# SchematProcesor.net
KiCad netlist of a schematic drawn in EAGLE
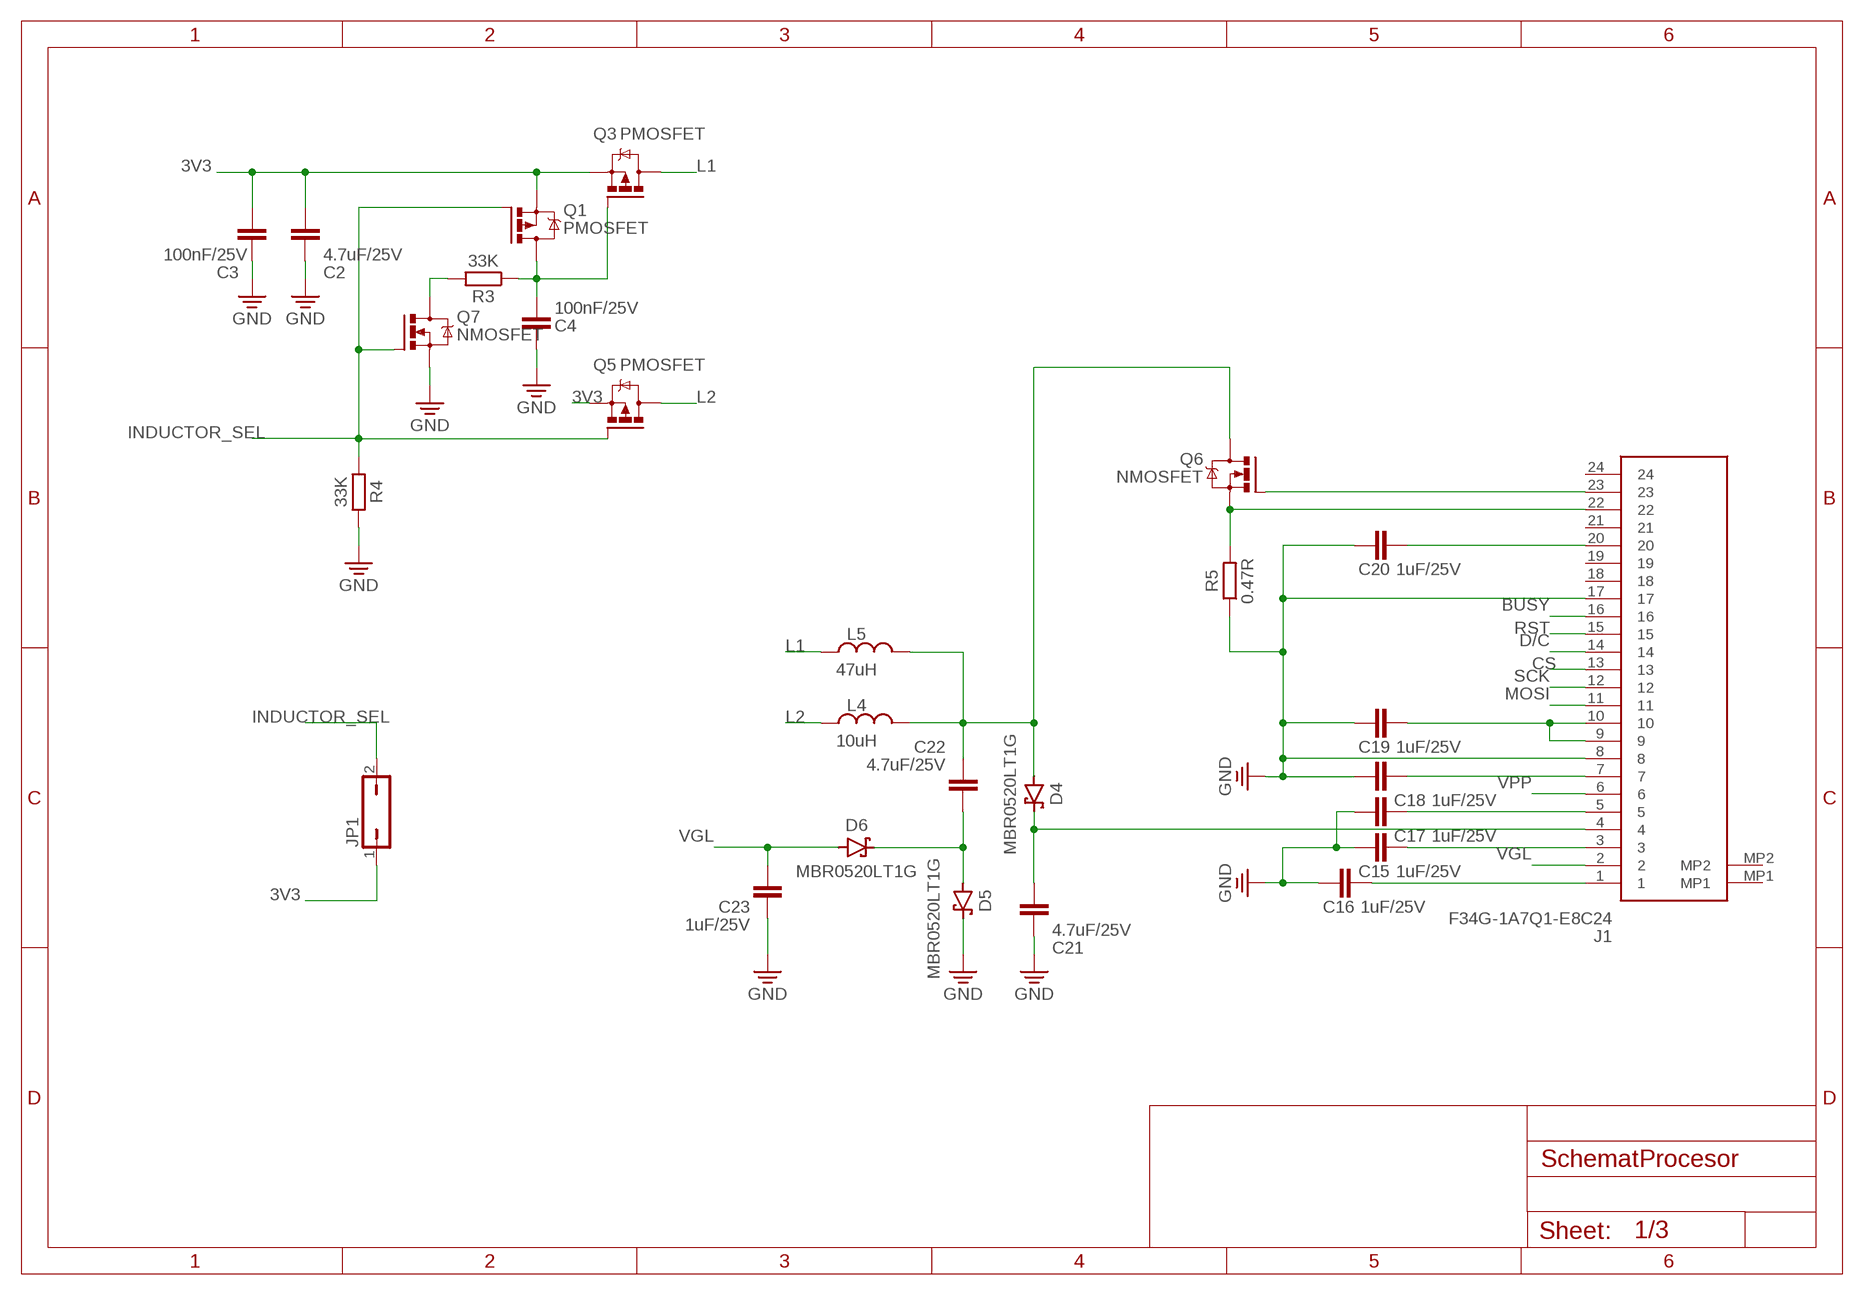
[diagram p0: schematic, sheet 1]
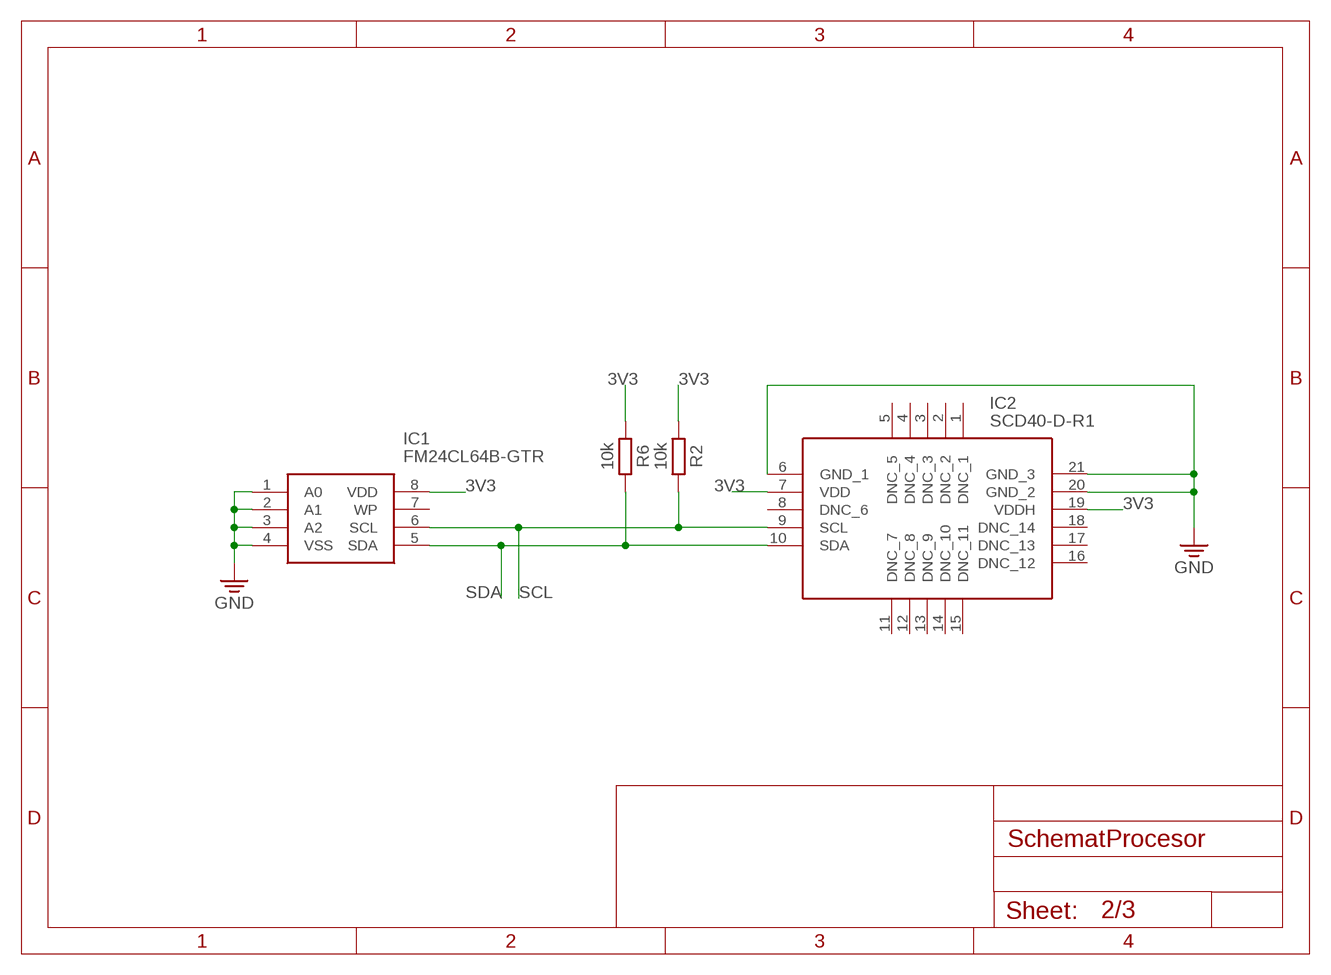
[diagram p1: schematic, sheet 2]
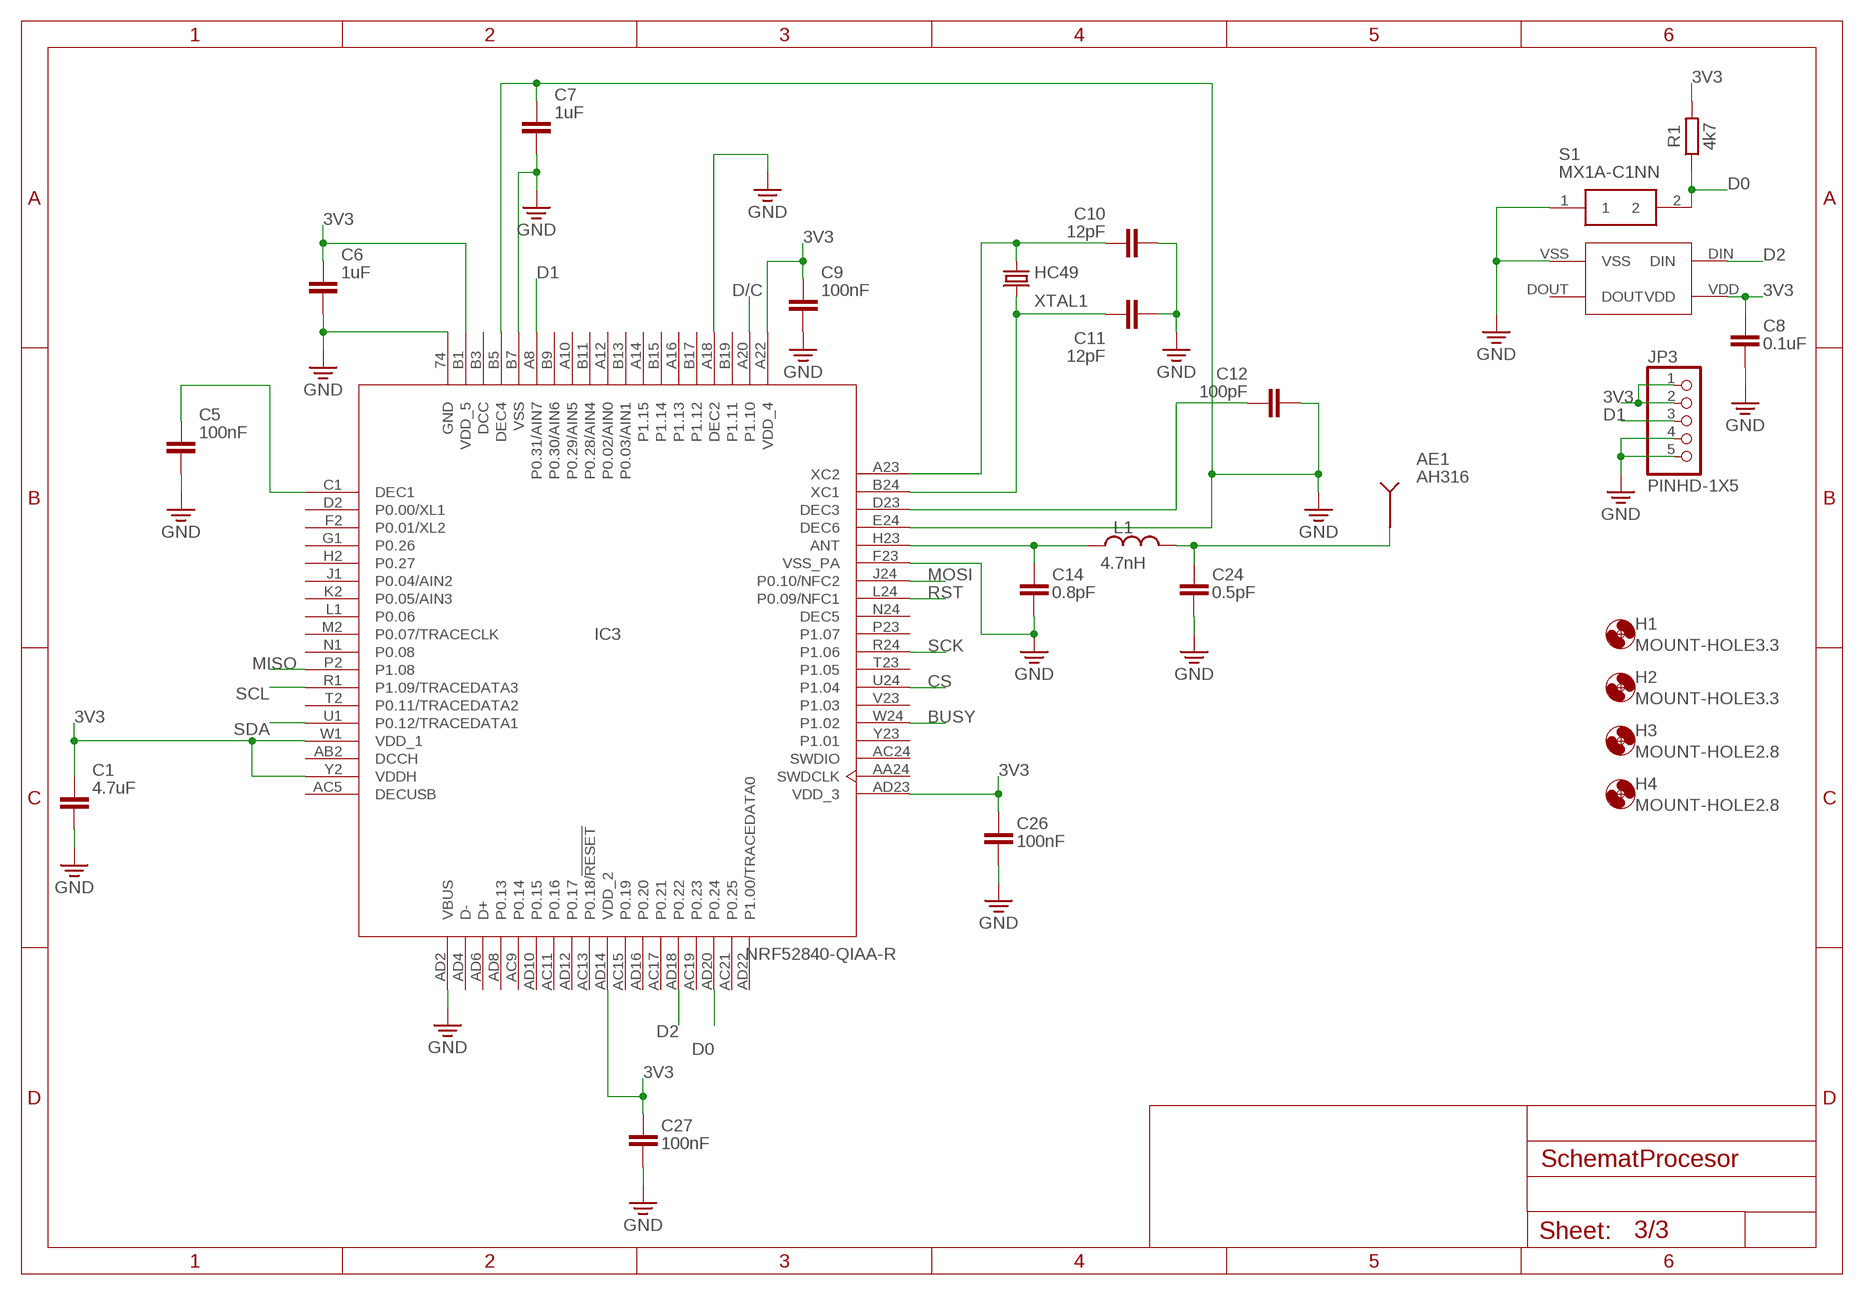
[diagram p2: schematic, sheet 3]

(export (version "E")
  (design (tool "Eeschema 10.0.6"))
  (components
    (comp (ref "C2")
      (value "4.7uF/25V")
      (footprint "eagle-import:CAPC1608X85")
      (libsource (lib "eagle-import") (part "CCHIP-0603(1608-METRIC)_"))
    )
    (comp (ref "C3")
      (value "100nF/25V")
      (footprint "eagle-import:CAPC1608X85")
      (libsource (lib "eagle-import") (part "CCHIP-0603(1608-METRIC)_"))
    )
    (comp (ref "C4")
      (value "100nF/25V")
      (footprint "eagle-import:CAPC1608X85")
      (libsource (lib "eagle-import") (part "CCHIP-0603(1608-METRIC)_"))
    )
    (comp (ref "C15")
      (value "1uF/25V")
      (footprint "eagle-import:CAPC1608X85")
      (libsource (lib "eagle-import") (part "CCHIP-0603(1608-METRIC)_"))
    )
    (comp (ref "C16")
      (value "1uF/25V")
      (footprint "eagle-import:CAPC1608X85")
      (libsource (lib "eagle-import") (part "CCHIP-0603(1608-METRIC)_"))
    )
    (comp (ref "C17")
      (value "1uF/25V")
      (footprint "eagle-import:CAPC1608X85")
      (libsource (lib "eagle-import") (part "CCHIP-0603(1608-METRIC)_"))
    )
    (comp (ref "C18")
      (value "1uF/25V")
      (footprint "eagle-import:CAPC1608X85")
      (libsource (lib "eagle-import") (part "CCHIP-0603(1608-METRIC)_"))
    )
    (comp (ref "C19")
      (value "1uF/25V")
      (footprint "eagle-import:CAPC1608X85")
      (libsource (lib "eagle-import") (part "CCHIP-0603(1608-METRIC)_"))
    )
    (comp (ref "C20")
      (value "1uF/25V")
      (footprint "eagle-import:CAPC1608X85")
      (libsource (lib "eagle-import") (part "CCHIP-0603(1608-METRIC)_"))
    )
    (comp (ref "C21")
      (value "4.7uF/25V")
      (footprint "eagle-import:CAPC1608X85")
      (libsource (lib "eagle-import") (part "CCHIP-0603(1608-METRIC)_"))
    )
    (comp (ref "C22")
      (value "4.7uF/25V")
      (footprint "eagle-import:CAPC1608X85")
      (libsource (lib "eagle-import") (part "CCHIP-0603(1608-METRIC)_"))
    )
    (comp (ref "C23")
      (value "1uF/25V")
      (footprint "eagle-import:CAPC1608X85")
      (libsource (lib "eagle-import") (part "CCHIP-0603(1608-METRIC)_"))
    )
    (comp (ref "D4")
      (value "MBR0520LT1G")
      (footprint "eagle-import:SODFL3718X115")
      (fields (field (name "MANUFACTURER") "ON Semiconductor"))
      (libsource (lib "eagle-import") (part "SCHOTTKY_DO-219MBR0520LT1G"))
    )
    (comp (ref "D5")
      (value "MBR0520LT1G")
      (footprint "eagle-import:SODFL3718X115")
      (fields (field (name "MANUFACTURER") "ON Semiconductor"))
      (libsource (lib "eagle-import") (part "SCHOTTKY_DO-219MBR0520LT1G"))
    )
    (comp (ref "D6")
      (value "MBR0520LT1G")
      (footprint "eagle-import:SODFL3718X115")
      (fields (field (name "MANUFACTURER") "ON Semiconductor"))
      (libsource (lib "eagle-import") (part "SCHOTTKY_DO-219MBR0520LT1G"))
    )
    (comp (ref "J1")
      (value "F34G-1A7Q1-E8C24")
      (footprint "eagle-import:F34G1A7Q1E8C24")
      (fields (field (name "MOUSER_PART_NUMBER") "649-F34G1A7Q1E8C24"))
      (libsource (lib "eagle-import") (part "F34G-1A7Q1-E8C24"))
    )
    (comp (ref "JP1")
      (value "JP1Q")
      (footprint "eagle-import:JP1")
      (libsource (lib "eagle-import") (part "JP1Q"))
    )
    (comp (ref "L4")
      (value "10uH")
      (footprint "eagle-import:INDC1608X95N")
      (libsource (lib "eagle-import") (part "LCHIP-0603(1608-METRIC)_"))
    )
    (comp (ref "L5")
      (value "47uH")
      (footprint "eagle-import:INDC1608X95N")
      (libsource (lib "eagle-import") (part "LCHIP-0603(1608-METRIC)_"))
    )
    (comp (ref "Q1")
      (value "PMOSFET")
      (footprint "eagle-import:SOT23")
      (libsource (lib "eagle-import") (part "PMOSFETSOT23-GSD_"))
    )
    (comp (ref "Q3")
      (value "PMOSFET")
      (footprint "eagle-import:SOT23")
      (libsource (lib "eagle-import") (part "PMOSFETSOT23-GSD_"))
    )
    (comp (ref "Q5")
      (value "PMOSFET")
      (footprint "eagle-import:SOT23")
      (libsource (lib "eagle-import") (part "PMOSFETSOT23-GSD_"))
    )
    (comp (ref "Q6")
      (value "NMOSFET")
      (footprint "eagle-import:SOT23")
      (libsource (lib "eagle-import") (part "NMOSFETSOT23-GSD"))
    )
    (comp (ref "Q7")
      (value "NMOSFET")
      (footprint "eagle-import:SOT23")
      (libsource (lib "eagle-import") (part "NMOSFETSOT23-GSD"))
    )
    (comp (ref "R3")
      (value "33K")
      (footprint "eagle-import:RESC1608X60")
      (libsource (lib "eagle-import") (part "RCHIP-0603(1608-METRIC)_"))
    )
    (comp (ref "R4")
      (value "33K")
      (footprint "eagle-import:RESC1608X60")
      (libsource (lib "eagle-import") (part "RCHIP-0603(1608-METRIC)_"))
    )
    (comp (ref "R5")
      (value "0.47R")
      (footprint "eagle-import:RESC1608X60")
      (libsource (lib "eagle-import") (part "RCHIP-0603(1608-METRIC)_"))
    )
    (comp (ref "IC1")
      (value "FM24CL64B-GTR")
      (footprint "eagle-import:SOIC127P602X173-8N")
      (fields (field (name "MOUSER_PART_NUMBER") "877-FM24CL64B-GTR"))
      (libsource (lib "eagle-import") (part "FM24CL64B-GTR"))
    )
    (comp (ref "IC2")
      (value "SCD40-D-R1")
      (footprint "eagle-import:SCD40DR1")
      (fields (field (name "MOUSER_PART_NUMBER") "403-SCD40-D-R1"))
      (libsource (lib "eagle-import") (part "SCD40-D-R1"))
    )
    (comp (ref "R2")
      (value "10k")
      (footprint "eagle-import:RESC1608X60")
      (libsource (lib "eagle-import") (part "RCHIP-0603(1608-METRIC)_"))
    )
    (comp (ref "R6")
      (value "10k")
      (footprint "eagle-import:RESC1608X60")
      (libsource (lib "eagle-import") (part "RCHIP-0603(1608-METRIC)_"))
    )
    (comp (ref "AE1")
      (value "AH316")
      (footprint "eagle-import:ANT-GPS-3.2X1MM")
      (fields (field (name "MANUFACTURER") "Taiyo Yuden") (field (name "MPN") "AH316M245001-T"))
      (libsource (lib "eagle-import") (part "AH316"))
    )
    (comp (ref "C1")
      (value "4.7uF")
      (footprint "eagle-import:CAPC1608X85")
      (libsource (lib "eagle-import") (part "CCHIP-0603(1608-METRIC)_"))
    )
    (comp (ref "C5")
      (value "100nF")
      (footprint "eagle-import:CAPC1608X85")
      (libsource (lib "eagle-import") (part "CCHIP-0603(1608-METRIC)_"))
    )
    (comp (ref "C6")
      (value "1uF")
      (footprint "eagle-import:CAPC1608X85")
      (libsource (lib "eagle-import") (part "CCHIP-0603(1608-METRIC)_"))
    )
    (comp (ref "C7")
      (value "1uF")
      (footprint "eagle-import:CAPC1608X85")
      (libsource (lib "eagle-import") (part "CCHIP-0603(1608-METRIC)_"))
    )
    (comp (ref "C8")
      (value "0.1uF")
      (footprint "eagle-import:CAPC1608X85")
      (libsource (lib "eagle-import") (part "CCHIP-0603(1608-METRIC)_"))
    )
    (comp (ref "C9")
      (value "100nF")
      (footprint "eagle-import:CAPC1608X85")
      (libsource (lib "eagle-import") (part "CCHIP-0603(1608-METRIC)_"))
    )
    (comp (ref "C10")
      (value "12pF")
      (footprint "eagle-import:CAPC1608X85")
      (libsource (lib "eagle-import") (part "CCHIP-0603(1608-METRIC)_"))
    )
    (comp (ref "C11")
      (value "12pF")
      (footprint "eagle-import:CAPC1608X85")
      (libsource (lib "eagle-import") (part "CCHIP-0603(1608-METRIC)_"))
    )
    (comp (ref "C12")
      (value "100pF")
      (footprint "eagle-import:CAPC1608X85")
      (libsource (lib "eagle-import") (part "CCHIP-0603(1608-METRIC)_"))
    )
    (comp (ref "C14")
      (value "0.8pF")
      (footprint "eagle-import:CAPC1608X85")
      (libsource (lib "eagle-import") (part "CCHIP-0603(1608-METRIC)_"))
    )
    (comp (ref "C24")
      (value "0.5pF")
      (footprint "eagle-import:CAPC1608X85")
      (libsource (lib "eagle-import") (part "CCHIP-0603(1608-METRIC)_"))
    )
    (comp (ref "C26")
      (value "100nF")
      (footprint "eagle-import:CAPC1608X85")
      (libsource (lib "eagle-import") (part "CCHIP-0603(1608-METRIC)_"))
    )
    (comp (ref "C27")
      (value "100nF")
      (footprint "eagle-import:CAPC1608X85")
      (libsource (lib "eagle-import") (part "CCHIP-0603(1608-METRIC)_"))
    )
    (comp (ref "H1")
      (value "MOUNT-HOLE3.3")
      (footprint "eagle-import:3,3")
      (libsource (lib "eagle-import") (part "MOUNT-HOLE3.3"))
    )
    (comp (ref "H2")
      (value "MOUNT-HOLE3.3")
      (footprint "eagle-import:3,3")
      (libsource (lib "eagle-import") (part "MOUNT-HOLE3.3"))
    )
    (comp (ref "H3")
      (value "MOUNT-HOLE2.8")
      (footprint "eagle-import:2,8")
      (libsource (lib "eagle-import") (part "MOUNT-HOLE2.8"))
    )
    (comp (ref "H4")
      (value "MOUNT-HOLE2.8")
      (footprint "eagle-import:2,8")
      (libsource (lib "eagle-import") (part "MOUNT-HOLE2.8"))
    )
    (comp (ref "IC3")
      (value "NRF52840-QIAA-R")
      (footprint "eagle-import:NRF52840-QIAA")
      (fields (field (name "MANUFACTURER") "Nordic Semiconductor") (field (name "MPN") "nRF52840-QIAA-R"))
      (libsource (lib "eagle-import") (part "NRF52840-QIAA-R"))
    )
    (comp (ref "JP3")
      (value "PINHD-1X5")
      (footprint "eagle-import:1X05")
      (fields (field (name "MANUFACTURER") "Generic"))
      (libsource (lib "eagle-import") (part "PINHD-1X5"))
    )
    (comp (ref "L1")
      (value "4.7nH")
      (footprint "eagle-import:INDC1608X95N")
      (libsource (lib "eagle-import") (part "LCHIP-0603(1608-METRIC)_"))
    )
    (comp (ref "R1")
      (value "4k7")
      (footprint "eagle-import:RESC1005X40")
      (libsource (lib "eagle-import") (part "RCHIP-0402(1005-METRIC)_"))
    )
    (comp (ref "S1")
      (value "MX1A-C1NN")
      (footprint "eagle-import:MX1AC1NN")
      (fields (field (name "MOUSER_PART_NUMBER") "540-MX1A-C1NN"))
      (libsource (lib "eagle-import") (part "MX1A-C1NN"))
    )
    (comp (ref "U$1")
      (value "N0M59S10IC")
      (footprint "eagle-import:N0M59S10IC")
      (libsource (lib "eagle-import") (part "N0M59S10IC"))
    )
    (comp (ref "XTAL1")
      (value "HC49")
      (footprint "eagle-import:XTALRR488W45L1150T500H350B")
      (libsource (lib "eagle-import") (part "CRYSTALHC49-11.5L_"))
    )
  )
  (nets
    (net (code "1") (name "3V3") (class "Default")
      (node (ref "C1") (pin "1") (pinfunction "1_1") (pintype "passive"))
      (node (ref "C2") (pin "2") (pinfunction "2_2") (pintype "passive"))
      (node (ref "C26") (pin "1") (pinfunction "1_1") (pintype "passive"))
      (node (ref "C27") (pin "1") (pinfunction "1_1") (pintype "passive"))
      (node (ref "C3") (pin "2") (pinfunction "2_2") (pintype "passive"))
      (node (ref "C6") (pin "1") (pinfunction "1_1") (pintype "passive"))
      (node (ref "C8") (pin "1") (pinfunction "1_1") (pintype "passive"))
      (node (ref "C9") (pin "1") (pinfunction "1_1") (pintype "passive"))
      (node (ref "IC1") (pin "8") (pinfunction "VDD_8") (pintype "bidirectional"))
      (node (ref "IC2") (pin "19") (pinfunction "VDDH_19") (pintype "bidirectional"))
      (node (ref "IC2") (pin "7") (pinfunction "VDD_7") (pintype "bidirectional"))
      (node (ref "IC3") (pin "A22") (pinfunction "VDD_4_A22") (pintype "power_in"))
      (node (ref "IC3") (pin "AD14") (pinfunction "VDD_2_AD14") (pintype "power_in"))
      (node (ref "IC3") (pin "AD23") (pinfunction "VDD_3_AD23") (pintype "power_in"))
      (node (ref "IC3") (pin "B1") (pinfunction "VDD_5_B1") (pintype "power_in"))
      (node (ref "IC3") (pin "W1") (pinfunction "VDD_1_W1") (pintype "power_in"))
      (node (ref "IC3") (pin "Y2") (pinfunction "VDDH_Y2") (pintype "power_in"))
      (node (ref "JP1") (pin "1") (pinfunction "1_1") (pintype "passive"))
      (node (ref "JP3") (pin "1") (pinfunction "1_1") (pintype "passive"))
      (node (ref "JP3") (pin "2") (pinfunction "2_2") (pintype "passive"))
      (node (ref "Q1") (pin "2") (pinfunction "S_2") (pintype "passive"))
      (node (ref "Q3") (pin "2") (pinfunction "S_2") (pintype "passive"))
      (node (ref "Q5") (pin "2") (pinfunction "S_2") (pintype "passive"))
      (node (ref "R1") (pin "2") (pinfunction "2_2") (pintype "passive"))
      (node (ref "R2") (pin "1") (pinfunction "1_1") (pintype "passive"))
      (node (ref "R6") (pin "1") (pinfunction "1_1") (pintype "passive"))
      (node (ref "U$1") (pin "VDD") (pinfunction "VDD_VDD") (pintype "bidirectional"))
    )
    (net (code "2") (name "BUSY") (class "Default")
      (node (ref "IC3") (pin "W24") (pinfunction "P1.02_W24") (pintype "bidirectional"))
      (node (ref "J1") (pin "16") (pinfunction "16_16") (pintype "bidirectional"))
    )
    (net (code "3") (name "CS") (class "Default")
      (node (ref "IC3") (pin "U24") (pinfunction "P1.04_U24") (pintype "bidirectional"))
      (node (ref "J1") (pin "13") (pinfunction "13_13") (pintype "bidirectional"))
    )
    (net (code "4") (name "D0") (class "Default")
      (node (ref "IC3") (pin "AD20") (pinfunction "P0.24_AD20") (pintype "bidirectional"))
      (node (ref "R1") (pin "1") (pinfunction "1_1") (pintype "passive"))
      (node (ref "S1") (pin "2") (pinfunction "2_2") (pintype "bidirectional"))
    )
    (net (code "5") (name "D1") (class "Default")
      (node (ref "IC3") (pin "A8") (pinfunction "P0.31/AIN7_A8") (pintype "bidirectional"))
      (node (ref "JP3") (pin "3") (pinfunction "3_3") (pintype "passive"))
    )
    (net (code "6") (name "D2") (class "Default")
      (node (ref "IC3") (pin "AD18") (pinfunction "P0.22_AD18") (pintype "bidirectional"))
      (node (ref "U$1") (pin "DIN") (pinfunction "DIN_DIN") (pintype "bidirectional"))
    )
    (net (code "7") (name "DCC") (class "Default")
      (node (ref "IC3") (pin "B3") (pinfunction "DCC_B3") (pintype "power_in"))
    )
    (net (code "8") (name "DCCH") (class "Default")
      (node (ref "IC3") (pin "AB2") (pinfunction "DCCH_AB2") (pintype "power_in"))
    )
    (net (code "9") (name "DEC5") (class "Default")
      (node (ref "IC3") (pin "N24") (pinfunction "DEC5_N24") (pintype "power_in"))
    )
    (net (code "10") (name "DECUSB") (class "Default")
      (node (ref "IC3") (pin "AC5") (pinfunction "DECUSB_AC5") (pintype "power_in"))
    )
    (net (code "11") (name "D{slash}C") (class "Default")
      (node (ref "IC3") (pin "A20") (pinfunction "P1.10_A20") (pintype "bidirectional"))
      (node (ref "J1") (pin "14") (pinfunction "14_14") (pintype "bidirectional"))
    )
    (net (code "12") (name "GND") (class "Default")
      (node (ref "C1") (pin "2") (pinfunction "2_2") (pintype "passive"))
      (node (ref "C10") (pin "2") (pinfunction "2_2") (pintype "passive"))
      (node (ref "C11") (pin "2") (pinfunction "2_2") (pintype "passive"))
      (node (ref "C12") (pin "2") (pinfunction "2_2") (pintype "passive"))
      (node (ref "C14") (pin "2") (pinfunction "2_2") (pintype "passive"))
      (node (ref "C15") (pin "1") (pinfunction "1_1") (pintype "passive"))
      (node (ref "C16") (pin "1") (pinfunction "1_1") (pintype "passive"))
      (node (ref "C17") (pin "1") (pinfunction "1_1") (pintype "passive"))
      (node (ref "C18") (pin "1") (pinfunction "1_1") (pintype "passive"))
      (node (ref "C19") (pin "1") (pinfunction "1_1") (pintype "passive"))
      (node (ref "C2") (pin "1") (pinfunction "1_1") (pintype "passive"))
      (node (ref "C20") (pin "1") (pinfunction "1_1") (pintype "passive"))
      (node (ref "C21") (pin "1") (pinfunction "1_1") (pintype "passive"))
      (node (ref "C23") (pin "2") (pinfunction "2_2") (pintype "passive"))
      (node (ref "C24") (pin "2") (pinfunction "2_2") (pintype "passive"))
      (node (ref "C26") (pin "2") (pinfunction "2_2") (pintype "passive"))
      (node (ref "C27") (pin "2") (pinfunction "2_2") (pintype "passive"))
      (node (ref "C3") (pin "1") (pinfunction "1_1") (pintype "passive"))
      (node (ref "C4") (pin "1") (pinfunction "1_1") (pintype "passive"))
      (node (ref "C5") (pin "2") (pinfunction "2_2") (pintype "passive"))
      (node (ref "C6") (pin "2") (pinfunction "2_2") (pintype "passive"))
      (node (ref "C7") (pin "1") (pinfunction "1_1") (pintype "passive"))
      (node (ref "C7") (pin "2") (pinfunction "2_2") (pintype "passive"))
      (node (ref "C8") (pin "2") (pinfunction "2_2") (pintype "passive"))
      (node (ref "C9") (pin "2") (pinfunction "2_2") (pintype "passive"))
      (node (ref "D5") (pin "1") (pinfunction "C_1") (pintype "passive"))
      (node (ref "IC1") (pin "1") (pinfunction "A0_1") (pintype "bidirectional"))
      (node (ref "IC1") (pin "2") (pinfunction "A1_2") (pintype "bidirectional"))
      (node (ref "IC1") (pin "3") (pinfunction "A2_3") (pintype "bidirectional"))
      (node (ref "IC1") (pin "4") (pinfunction "VSS_4") (pintype "bidirectional"))
      (node (ref "IC2") (pin "20") (pinfunction "GND_2_20") (pintype "bidirectional"))
      (node (ref "IC2") (pin "21") (pinfunction "GND_3_21") (pintype "bidirectional"))
      (node (ref "IC2") (pin "6") (pinfunction "GND_1_6") (pintype "bidirectional"))
      (node (ref "IC3") (pin "74") (pinfunction "GND_74") (pintype "power_in"))
      (node (ref "IC3") (pin "A18") (pinfunction "DEC2_A18") (pintype "power_in"))
      (node (ref "IC3") (pin "AD2") (pinfunction "VBUS_AD2") (pintype "power_in"))
      (node (ref "IC3") (pin "B5") (pinfunction "DEC4_B5") (pintype "power_in"))
      (node (ref "IC3") (pin "B7") (pinfunction "VSS_B7") (pintype "power_in"))
      (node (ref "IC3") (pin "E24") (pinfunction "DEC6_E24") (pintype "power_in"))
      (node (ref "IC3") (pin "F23") (pinfunction "VSS_PA_F23") (pintype "power_in"))
      (node (ref "J1") (pin "17") (pinfunction "17_17") (pintype "bidirectional"))
      (node (ref "J1") (pin "8") (pinfunction "8_8") (pintype "bidirectional"))
      (node (ref "JP3") (pin "4") (pinfunction "4_4") (pintype "passive"))
      (node (ref "JP3") (pin "5") (pinfunction "5_5") (pintype "passive"))
      (node (ref "Q7") (pin "2") (pinfunction "S_2") (pintype "passive"))
      (node (ref "R4") (pin "2") (pinfunction "2_2") (pintype "passive"))
      (node (ref "R5") (pin "1") (pinfunction "1_1") (pintype "passive"))
      (node (ref "S1") (pin "1") (pinfunction "1_1") (pintype "bidirectional"))
      (node (ref "U$1") (pin "VSS") (pinfunction "VSS_VSS") (pintype "bidirectional"))
    )
    (net (code "13") (name "INDUCTOR_SEL") (class "Default")
      (node (ref "JP1") (pin "2") (pinfunction "2_2") (pintype "passive"))
      (node (ref "Q1") (pin "1") (pinfunction "G_1") (pintype "passive"))
      (node (ref "Q5") (pin "1") (pinfunction "G_1") (pintype "passive"))
      (node (ref "Q7") (pin "1") (pinfunction "G_1") (pintype "passive"))
      (node (ref "R4") (pin "1") (pinfunction "1_1") (pintype "passive"))
    )
    (net (code "14") (name "L1") (class "Default")
      (node (ref "L5") (pin "1") (pinfunction "1_1") (pintype "passive"))
      (node (ref "Q3") (pin "3") (pinfunction "D_3") (pintype "passive"))
    )
    (net (code "15") (name "L2") (class "Default")
      (node (ref "L4") (pin "1") (pinfunction "1_1") (pintype "passive"))
      (node (ref "Q5") (pin "3") (pinfunction "D_3") (pintype "passive"))
    )
    (net (code "16") (name "MISO") (class "Default")
      (node (ref "IC3") (pin "P2") (pinfunction "P1.08_P2") (pintype "bidirectional"))
    )
    (net (code "17") (name "MOSI") (class "Default")
      (node (ref "IC3") (pin "J24") (pinfunction "P0.10/NFC2_J24") (pintype "bidirectional"))
      (node (ref "J1") (pin "11") (pinfunction "11_11") (pintype "bidirectional"))
    )
    (net (code "18") (name "Net-(AE1-GND)") (class "Default")
      (node (ref "AE1") (pin "2") (pinfunction "GND_2") (pintype "bidirectional"))
      (node (ref "C24") (pin "1") (pinfunction "1_1") (pintype "passive"))
      (node (ref "L1") (pin "2") (pinfunction "2_2") (pintype "passive"))
    )
    (net (code "19") (name "Net-(C15-Pad2)") (class "Default")
      (node (ref "C15") (pin "2") (pinfunction "2_2") (pintype "passive"))
      (node (ref "J1") (pin "3") (pinfunction "3_3") (pintype "bidirectional"))
    )
    (net (code "20") (name "Net-(C16-Pad2)") (class "Default")
      (node (ref "C16") (pin "2") (pinfunction "2_2") (pintype "passive"))
      (node (ref "J1") (pin "1") (pinfunction "1_1") (pintype "bidirectional"))
    )
    (net (code "21") (name "Net-(C17-Pad2)") (class "Default")
      (node (ref "C17") (pin "2") (pinfunction "2_2") (pintype "passive"))
      (node (ref "J1") (pin "5") (pinfunction "5_5") (pintype "bidirectional"))
    )
    (net (code "22") (name "Net-(C18-Pad2)") (class "Default")
      (node (ref "C18") (pin "2") (pinfunction "2_2") (pintype "passive"))
      (node (ref "J1") (pin "7") (pinfunction "7_7") (pintype "bidirectional"))
    )
    (net (code "23") (name "Net-(C19-Pad2)") (class "Default")
      (node (ref "C19") (pin "2") (pinfunction "2_2") (pintype "passive"))
      (node (ref "J1") (pin "10") (pinfunction "10_10") (pintype "bidirectional"))
      (node (ref "J1") (pin "9") (pinfunction "9_9") (pintype "bidirectional"))
    )
    (net (code "24") (name "Net-(C20-Pad2)") (class "Default")
      (node (ref "C20") (pin "2") (pinfunction "2_2") (pintype "passive"))
      (node (ref "J1") (pin "20") (pinfunction "20_20") (pintype "bidirectional"))
    )
    (net (code "25") (name "Net-(D4-A)") (class "Default")
      (node (ref "C22") (pin "1") (pinfunction "1_1") (pintype "passive"))
      (node (ref "D4") (pin "2") (pinfunction "A_2") (pintype "passive"))
      (node (ref "L4") (pin "2") (pinfunction "2_2") (pintype "passive"))
      (node (ref "L5") (pin "2") (pinfunction "2_2") (pintype "passive"))
      (node (ref "Q6") (pin "3") (pinfunction "D_3") (pintype "passive"))
    )
    (net (code "26") (name "Net-(D4-C)") (class "Default")
      (node (ref "C21") (pin "2") (pinfunction "2_2") (pintype "passive"))
      (node (ref "D4") (pin "1") (pinfunction "C_1") (pintype "passive"))
      (node (ref "J1") (pin "4") (pinfunction "4_4") (pintype "bidirectional"))
    )
    (net (code "27") (name "Net-(D5-A)") (class "Default")
      (node (ref "C22") (pin "2") (pinfunction "2_2") (pintype "passive"))
      (node (ref "D5") (pin "2") (pinfunction "A_2") (pintype "passive"))
      (node (ref "D6") (pin "1") (pinfunction "C_1") (pintype "passive"))
    )
    (net (code "28") (name "Net-(IC3-ANT)") (class "Default")
      (node (ref "C14") (pin "1") (pinfunction "1_1") (pintype "passive"))
      (node (ref "IC3") (pin "H23") (pinfunction "ANT_H23") (pintype "bidirectional"))
      (node (ref "L1") (pin "1") (pinfunction "1_1") (pintype "passive"))
    )
    (net (code "29") (name "Net-(IC3-DEC1)") (class "Default")
      (node (ref "C5") (pin "1") (pinfunction "1_1") (pintype "passive"))
      (node (ref "IC3") (pin "C1") (pinfunction "DEC1_C1") (pintype "power_in"))
    )
    (net (code "30") (name "Net-(IC3-DEC3)") (class "Default")
      (node (ref "C12") (pin "1") (pinfunction "1_1") (pintype "passive"))
      (node (ref "IC3") (pin "D23") (pinfunction "DEC3_D23") (pintype "power_in"))
    )
    (net (code "31") (name "Net-(IC3-XC1)") (class "Default")
      (node (ref "C11") (pin "1") (pinfunction "1_1") (pintype "passive"))
      (node (ref "IC3") (pin "B24") (pinfunction "XC1_B24") (pintype "input"))
      (node (ref "XTAL1") (pin "2") (pinfunction "2_2") (pintype "passive"))
    )
    (net (code "32") (name "Net-(IC3-XC2)") (class "Default")
      (node (ref "C10") (pin "1") (pinfunction "1_1") (pintype "passive"))
      (node (ref "IC3") (pin "A23") (pinfunction "XC2_A23") (pintype "input"))
      (node (ref "XTAL1") (pin "1") (pinfunction "1_1") (pintype "passive"))
    )
    (net (code "33") (name "Net-(Q1-D)") (class "Default")
      (node (ref "C4") (pin "2") (pinfunction "2_2") (pintype "passive"))
      (node (ref "Q1") (pin "3") (pinfunction "D_3") (pintype "passive"))
      (node (ref "Q3") (pin "1") (pinfunction "G_1") (pintype "passive"))
      (node (ref "R3") (pin "1") (pinfunction "1_1") (pintype "passive"))
    )
    (net (code "34") (name "Net-(Q6-G)") (class "Default")
      (node (ref "J1") (pin "23") (pinfunction "23_23") (pintype "bidirectional"))
      (node (ref "Q6") (pin "1") (pinfunction "G_1") (pintype "passive"))
    )
    (net (code "35") (name "Net-(Q6-S)") (class "Default")
      (node (ref "J1") (pin "22") (pinfunction "22_22") (pintype "bidirectional"))
      (node (ref "Q6") (pin "2") (pinfunction "S_2") (pintype "passive"))
      (node (ref "R5") (pin "2") (pinfunction "2_2") (pintype "passive"))
    )
    (net (code "36") (name "Net-(Q7-D)") (class "Default")
      (node (ref "Q7") (pin "3") (pinfunction "D_3") (pintype "passive"))
      (node (ref "R3") (pin "2") (pinfunction "2_2") (pintype "passive"))
    )
    (net (code "37") (name "RST") (class "Default")
      (node (ref "IC3") (pin "L24") (pinfunction "P0.09/NFC1_L24") (pintype "bidirectional"))
      (node (ref "J1") (pin "15") (pinfunction "15_15") (pintype "bidirectional"))
    )
    (net (code "38") (name "SCK") (class "Default")
      (node (ref "IC3") (pin "R24") (pinfunction "P1.06_R24") (pintype "bidirectional"))
      (node (ref "J1") (pin "12") (pinfunction "12_12") (pintype "bidirectional"))
    )
    (net (code "39") (name "SCL") (class "Default")
      (node (ref "IC1") (pin "6") (pinfunction "SCL_6") (pintype "bidirectional"))
      (node (ref "IC2") (pin "9") (pinfunction "SCL_9") (pintype "bidirectional"))
      (node (ref "IC3") (pin "R1") (pinfunction "P1.09/TRACEDATA3_R1") (pintype "bidirectional"))
      (node (ref "R2") (pin "2") (pinfunction "2_2") (pintype "passive"))
    )
    (net (code "40") (name "SDA") (class "Default")
      (node (ref "IC1") (pin "5") (pinfunction "SDA_5") (pintype "bidirectional"))
      (node (ref "IC2") (pin "10") (pinfunction "SDA_10") (pintype "bidirectional"))
      (node (ref "IC3") (pin "U1") (pinfunction "P0.12/TRACEDATA1_U1") (pintype "bidirectional"))
      (node (ref "R6") (pin "2") (pinfunction "2_2") (pintype "passive"))
    )
    (net (code "41") (name "VGL") (class "Default")
      (node (ref "C23") (pin "1") (pinfunction "1_1") (pintype "passive"))
      (node (ref "D6") (pin "2") (pinfunction "A_2") (pintype "passive"))
      (node (ref "J1") (pin "2") (pinfunction "2_2") (pintype "bidirectional"))
    )
    (net (code "42") (name "VPP") (class "Default")
      (node (ref "J1") (pin "6") (pinfunction "6_6") (pintype "bidirectional"))
    )
    (net (code "43") (name "unconnected-(AE1-SIG-Pad1)") (class "Default")
      (node (ref "AE1") (pin "1") (pinfunction "SIG_1") (pintype "input"))
    )
    (net (code "44") (name "unconnected-(IC1-WP-Pad7)") (class "Default")
      (node (ref "IC1") (pin "7") (pinfunction "WP_7") (pintype "bidirectional"))
    )
    (net (code "45") (name "unconnected-(IC2-DNC_1-Pad1)") (class "Default")
      (node (ref "IC2") (pin "1") (pinfunction "DNC_1_1") (pintype "bidirectional"))
    )
    (net (code "46") (name "unconnected-(IC2-DNC_2-Pad2)") (class "Default")
      (node (ref "IC2") (pin "2") (pinfunction "DNC_2_2") (pintype "bidirectional"))
    )
    (net (code "47") (name "unconnected-(IC2-DNC_3-Pad3)") (class "Default")
      (node (ref "IC2") (pin "3") (pinfunction "DNC_3_3") (pintype "bidirectional"))
    )
    (net (code "48") (name "unconnected-(IC2-DNC_4-Pad4)") (class "Default")
      (node (ref "IC2") (pin "4") (pinfunction "DNC_4_4") (pintype "bidirectional"))
    )
    (net (code "49") (name "unconnected-(IC2-DNC_5-Pad5)") (class "Default")
      (node (ref "IC2") (pin "5") (pinfunction "DNC_5_5") (pintype "bidirectional"))
    )
    (net (code "50") (name "unconnected-(IC2-DNC_6-Pad8)") (class "Default")
      (node (ref "IC2") (pin "8") (pinfunction "DNC_6_8") (pintype "bidirectional"))
    )
    (net (code "51") (name "unconnected-(IC2-DNC_7-Pad11)") (class "Default")
      (node (ref "IC2") (pin "11") (pinfunction "DNC_7_11") (pintype "bidirectional"))
    )
    (net (code "52") (name "unconnected-(IC2-DNC_8-Pad12)") (class "Default")
      (node (ref "IC2") (pin "12") (pinfunction "DNC_8_12") (pintype "bidirectional"))
    )
    (net (code "53") (name "unconnected-(IC2-DNC_9-Pad13)") (class "Default")
      (node (ref "IC2") (pin "13") (pinfunction "DNC_9_13") (pintype "bidirectional"))
    )
    (net (code "54") (name "unconnected-(IC2-DNC_10-Pad14)") (class "Default")
      (node (ref "IC2") (pin "14") (pinfunction "DNC_10_14") (pintype "bidirectional"))
    )
    (net (code "55") (name "unconnected-(IC2-DNC_11-Pad15)") (class "Default")
      (node (ref "IC2") (pin "15") (pinfunction "DNC_11_15") (pintype "bidirectional"))
    )
    (net (code "56") (name "unconnected-(IC2-DNC_12-Pad16)") (class "Default")
      (node (ref "IC2") (pin "16") (pinfunction "DNC_12_16") (pintype "bidirectional"))
    )
    (net (code "57") (name "unconnected-(IC2-DNC_13-Pad17)") (class "Default")
      (node (ref "IC2") (pin "17") (pinfunction "DNC_13_17") (pintype "bidirectional"))
    )
    (net (code "58") (name "unconnected-(IC2-DNC_14-Pad18)") (class "Default")
      (node (ref "IC2") (pin "18") (pinfunction "DNC_14_18") (pintype "bidirectional"))
    )
    (net (code "59") (name "unconnected-(IC3-D+-PadAD6)") (class "Default")
      (node (ref "IC3") (pin "AD6") (pinfunction "D+_AD6") (pintype "bidirectional"))
    )
    (net (code "60") (name "unconnected-(IC3-D--PadAD4)") (class "Default")
      (node (ref "IC3") (pin "AD4") (pinfunction "D-_AD4") (pintype "bidirectional"))
    )
    (net (code "61") (name "unconnected-(IC3-P0.00{slash}XL1-PadD2)") (class "Default")
      (node (ref "IC3") (pin "D2") (pinfunction "P0.00/XL1_D2") (pintype "bidirectional"))
    )
    (net (code "62") (name "unconnected-(IC3-P0.01{slash}XL2-PadF2)") (class "Default")
      (node (ref "IC3") (pin "F2") (pinfunction "P0.01/XL2_F2") (pintype "bidirectional"))
    )
    (net (code "63") (name "unconnected-(IC3-P0.02{slash}AIN0-PadA12)") (class "Default")
      (node (ref "IC3") (pin "A12") (pinfunction "P0.02/AIN0_A12") (pintype "bidirectional"))
    )
    (net (code "64") (name "unconnected-(IC3-P0.03{slash}AIN1-PadB13)") (class "Default")
      (node (ref "IC3") (pin "B13") (pinfunction "P0.03/AIN1_B13") (pintype "bidirectional"))
    )
    (net (code "65") (name "unconnected-(IC3-P0.04{slash}AIN2-PadJ1)") (class "Default")
      (node (ref "IC3") (pin "J1") (pinfunction "P0.04/AIN2_J1") (pintype "bidirectional"))
    )
    (net (code "66") (name "unconnected-(IC3-P0.05{slash}AIN3-PadK2)") (class "Default")
      (node (ref "IC3") (pin "K2") (pinfunction "P0.05/AIN3_K2") (pintype "bidirectional"))
    )
    (net (code "67") (name "unconnected-(IC3-P0.06-PadL1)") (class "Default")
      (node (ref "IC3") (pin "L1") (pinfunction "P0.06_L1") (pintype "bidirectional"))
    )
    (net (code "68") (name "unconnected-(IC3-P0.07{slash}TRACECLK-PadM2)") (class "Default")
      (node (ref "IC3") (pin "M2") (pinfunction "P0.07/TRACECLK_M2") (pintype "bidirectional"))
    )
    (net (code "69") (name "unconnected-(IC3-P0.08-PadN1)") (class "Default")
      (node (ref "IC3") (pin "N1") (pinfunction "P0.08_N1") (pintype "bidirectional"))
    )
    (net (code "70") (name "unconnected-(IC3-P0.11{slash}TRACEDATA2-PadT2)") (class "Default")
      (node (ref "IC3") (pin "T2") (pinfunction "P0.11/TRACEDATA2_T2") (pintype "bidirectional"))
    )
    (net (code "71") (name "unconnected-(IC3-P0.13-PadAD8)") (class "Default")
      (node (ref "IC3") (pin "AD8") (pinfunction "P0.13_AD8") (pintype "bidirectional"))
    )
    (net (code "72") (name "unconnected-(IC3-P0.14-PadAC9)") (class "Default")
      (node (ref "IC3") (pin "AC9") (pinfunction "P0.14_AC9") (pintype "bidirectional"))
    )
    (net (code "73") (name "unconnected-(IC3-P0.15-PadAD10)") (class "Default")
      (node (ref "IC3") (pin "AD10") (pinfunction "P0.15_AD10") (pintype "bidirectional"))
    )
    (net (code "74") (name "unconnected-(IC3-P0.16-PadAC11)") (class "Default")
      (node (ref "IC3") (pin "AC11") (pinfunction "P0.16_AC11") (pintype "bidirectional"))
    )
    (net (code "75") (name "unconnected-(IC3-P0.17-PadAD12)") (class "Default")
      (node (ref "IC3") (pin "AD12") (pinfunction "P0.17_AD12") (pintype "bidirectional"))
    )
    (net (code "76") (name "unconnected-(IC3-P0.18{slash}~{RESET}-PadAC13)") (class "Default")
      (node (ref "IC3") (pin "AC13") (pinfunction "P0.18/~{RESET}_AC13") (pintype "bidirectional"))
    )
    (net (code "77") (name "unconnected-(IC3-P0.19-PadAC15)") (class "Default")
      (node (ref "IC3") (pin "AC15") (pinfunction "P0.19_AC15") (pintype "bidirectional"))
    )
    (net (code "78") (name "unconnected-(IC3-P0.20-PadAD16)") (class "Default")
      (node (ref "IC3") (pin "AD16") (pinfunction "P0.20_AD16") (pintype "bidirectional"))
    )
    (net (code "79") (name "unconnected-(IC3-P0.21-PadAC17)") (class "Default")
      (node (ref "IC3") (pin "AC17") (pinfunction "P0.21_AC17") (pintype "bidirectional"))
    )
    (net (code "80") (name "unconnected-(IC3-P0.23-PadAC19)") (class "Default")
      (node (ref "IC3") (pin "AC19") (pinfunction "P0.23_AC19") (pintype "bidirectional"))
    )
    (net (code "81") (name "unconnected-(IC3-P0.25-PadAC21)") (class "Default")
      (node (ref "IC3") (pin "AC21") (pinfunction "P0.25_AC21") (pintype "bidirectional"))
    )
    (net (code "82") (name "unconnected-(IC3-P0.26-PadG1)") (class "Default")
      (node (ref "IC3") (pin "G1") (pinfunction "P0.26_G1") (pintype "bidirectional"))
    )
    (net (code "83") (name "unconnected-(IC3-P0.27-PadH2)") (class "Default")
      (node (ref "IC3") (pin "H2") (pinfunction "P0.27_H2") (pintype "bidirectional"))
    )
    (net (code "84") (name "unconnected-(IC3-P0.28{slash}AIN4-PadB11)") (class "Default")
      (node (ref "IC3") (pin "B11") (pinfunction "P0.28/AIN4_B11") (pintype "bidirectional"))
    )
    (net (code "85") (name "unconnected-(IC3-P0.29{slash}AIN5-PadA10)") (class "Default")
      (node (ref "IC3") (pin "A10") (pinfunction "P0.29/AIN5_A10") (pintype "bidirectional"))
    )
    (net (code "86") (name "unconnected-(IC3-P0.30{slash}AIN6-PadB9)") (class "Default")
      (node (ref "IC3") (pin "B9") (pinfunction "P0.30/AIN6_B9") (pintype "bidirectional"))
    )
    (net (code "87") (name "unconnected-(IC3-P1.00{slash}TRACEDATA0-PadAD22)") (class "Default")
      (node (ref "IC3") (pin "AD22") (pinfunction "P1.00/TRACEDATA0_AD22") (pintype "bidirectional"))
    )
    (net (code "88") (name "unconnected-(IC3-P1.01-PadY23)") (class "Default")
      (node (ref "IC3") (pin "Y23") (pinfunction "P1.01_Y23") (pintype "bidirectional"))
    )
    (net (code "89") (name "unconnected-(IC3-P1.03-PadV23)") (class "Default")
      (node (ref "IC3") (pin "V23") (pinfunction "P1.03_V23") (pintype "bidirectional"))
    )
    (net (code "90") (name "unconnected-(IC3-P1.05-PadT23)") (class "Default")
      (node (ref "IC3") (pin "T23") (pinfunction "P1.05_T23") (pintype "bidirectional"))
    )
    (net (code "91") (name "unconnected-(IC3-P1.07-PadP23)") (class "Default")
      (node (ref "IC3") (pin "P23") (pinfunction "P1.07_P23") (pintype "bidirectional"))
    )
    (net (code "92") (name "unconnected-(IC3-P1.11-PadB19)") (class "Default")
      (node (ref "IC3") (pin "B19") (pinfunction "P1.11_B19") (pintype "bidirectional"))
    )
    (net (code "93") (name "unconnected-(IC3-P1.12-PadB17)") (class "Default")
      (node (ref "IC3") (pin "B17") (pinfunction "P1.12_B17") (pintype "bidirectional"))
    )
    (net (code "94") (name "unconnected-(IC3-P1.13-PadA16)") (class "Default")
      (node (ref "IC3") (pin "A16") (pinfunction "P1.13_A16") (pintype "bidirectional"))
    )
    (net (code "95") (name "unconnected-(IC3-P1.14-PadB15)") (class "Default")
      (node (ref "IC3") (pin "B15") (pinfunction "P1.14_B15") (pintype "bidirectional"))
    )
    (net (code "96") (name "unconnected-(IC3-P1.15-PadA14)") (class "Default")
      (node (ref "IC3") (pin "A14") (pinfunction "P1.15_A14") (pintype "bidirectional"))
    )
    (net (code "97") (name "unconnected-(IC3-SWDCLK-PadAA24)") (class "Default")
      (node (ref "IC3") (pin "AA24") (pinfunction "SWDCLK_AA24") (pintype "input"))
    )
    (net (code "98") (name "unconnected-(IC3-SWDIO-PadAC24)") (class "Default")
      (node (ref "IC3") (pin "AC24") (pinfunction "SWDIO_AC24") (pintype "bidirectional"))
    )
    (net (code "99") (name "unconnected-(J1-Pad18)") (class "Default")
      (node (ref "J1") (pin "18") (pinfunction "18_18") (pintype "bidirectional"))
    )
    (net (code "100") (name "unconnected-(J1-Pad19)") (class "Default")
      (node (ref "J1") (pin "19") (pinfunction "19_19") (pintype "bidirectional"))
    )
    (net (code "101") (name "unconnected-(J1-Pad21)") (class "Default")
      (node (ref "J1") (pin "21") (pinfunction "21_21") (pintype "bidirectional"))
    )
    (net (code "102") (name "unconnected-(J1-Pad24)") (class "Default")
      (node (ref "J1") (pin "24") (pinfunction "24_24") (pintype "bidirectional"))
    )
    (net (code "103") (name "unconnected-(J1-PadMP1)") (class "Default")
      (node (ref "J1") (pin "MP1") (pinfunction "MP1_MP1") (pintype "bidirectional"))
    )
    (net (code "104") (name "unconnected-(J1-PadMP2)") (class "Default")
      (node (ref "J1") (pin "MP2") (pinfunction "MP2_MP2") (pintype "bidirectional"))
    )
    (net (code "105") (name "unconnected-(U$1-PadDOUT)") (class "Default")
      (node (ref "U$1") (pin "DOUT") (pinfunction "DOUT_DOUT") (pintype "bidirectional"))
    )
  )
)
